# AtxPowerDispatcher3.net
KiCad netlist of a schematic drawn in EAGLE
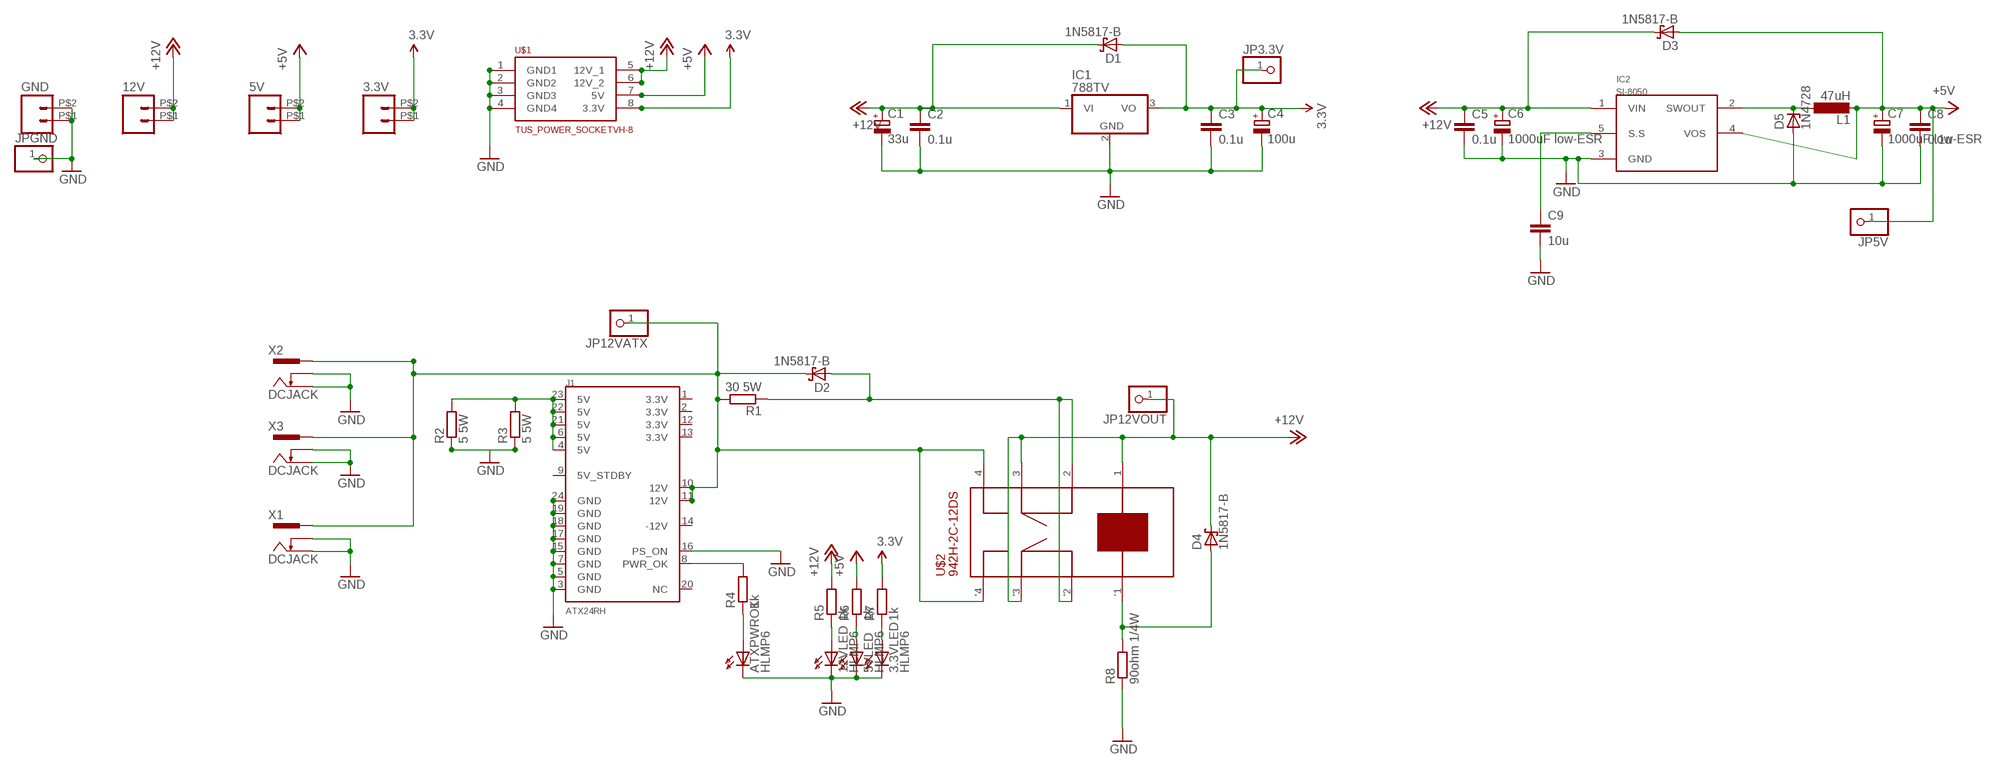
[diagram p0: schematic, sheet 1]

(export (version "E")
  (design (tool "Eeschema 10.0.6"))
  (components
    (comp (ref "3.3V")
      (value "M02PTH2")
      (footprint "eagle-import:1X02_BIG")
      (libsource (lib "eagle-import") (part "M02PTH2"))
    )
    (comp (ref "3.3VLED")
      (value "HLMP6")
      (footprint "eagle-import:HLMP6")
      (fields
        (field (name "MF") "AGILENT TECHNOLOGIES")
        (field (name "MPN") "HLMP-6500")
        (field (name "MF_1") "AGILENT TECHNOLOGIES")
        (field (name "MPN_1") "HLMP-6500")
        (field (name "OC_FARNELL") "1652490")
        (field (name "OC_NEWARK") "40K0088")
      )
      (libsource (lib "eagle-import") (part "HLMP6"))
    )
    (comp (ref "5V")
      (value "M02PTH2")
      (footprint "eagle-import:1X02_BIG")
      (libsource (lib "eagle-import") (part "M02PTH2"))
    )
    (comp (ref "5VLED")
      (value "HLMP6")
      (footprint "eagle-import:HLMP6")
      (fields
        (field (name "MF") "AGILENT TECHNOLOGIES")
        (field (name "MPN") "HLMP-6500")
        (field (name "MF_1") "AGILENT TECHNOLOGIES")
        (field (name "MPN_1") "HLMP-6500")
        (field (name "OC_FARNELL") "1652490")
        (field (name "OC_NEWARK") "40K0088")
      )
      (libsource (lib "eagle-import") (part "HLMP6"))
    )
    (comp (ref "12V")
      (value "M02PTH2")
      (footprint "eagle-import:1X02_BIG")
      (libsource (lib "eagle-import") (part "M02PTH2"))
    )
    (comp (ref "12VLED")
      (value "HLMP6")
      (footprint "eagle-import:HLMP6")
      (fields (field (name "MF") "AGILENT TECHNOLOGIES") (field (name "MPN") "HLMP-6500"))
      (libsource (lib "eagle-import") (part "HLMP6"))
    )
    (comp (ref "ATXPWROK")
      (value "HLMP6")
      (footprint "eagle-import:HLMP6")
      (fields
        (field (name "MF") "AGILENT TECHNOLOGIES")
        (field (name "MPN") "HLMP-6500")
        (field (name "MF_1") "AGILENT TECHNOLOGIES")
        (field (name "MPN_1") "HLMP-6500")
        (field (name "OC_FARNELL") "1652490")
        (field (name "OC_NEWARK") "40K0088")
      )
      (libsource (lib "eagle-import") (part "HLMP6"))
    )
    (comp (ref "C1")
      (value "33u")
      (footprint "eagle-import:E2,5-6E")
      (libsource (lib "eagle-import") (part "CPOL-EUE2,5-6E"))
    )
    (comp (ref "C2")
      (value "0.1u")
      (footprint "eagle-import:C0603")
      (libsource (lib "eagle-import") (part "C-EUC0603"))
    )
    (comp (ref "C3")
      (value "0.1u")
      (footprint "eagle-import:C0603")
      (libsource (lib "eagle-import") (part "C-EUC0603"))
    )
    (comp (ref "C4")
      (value "100u")
      (footprint "eagle-import:E2,5-6E")
      (libsource (lib "eagle-import") (part "CPOL-EUE2,5-6E"))
    )
    (comp (ref "C5")
      (value "0.1u")
      (footprint "eagle-import:C0603")
      (libsource (lib "eagle-import") (part "C-EUC0603"))
    )
    (comp (ref "C6")
      (value "1000uF low-ESR")
      (footprint "eagle-import:E5-10,5")
      (libsource (lib "eagle-import") (part "CPOL-EUE5-10.5"))
    )
    (comp (ref "C7")
      (value "1000uF low-ESR")
      (footprint "eagle-import:E5-10,5")
      (libsource (lib "eagle-import") (part "CPOL-EUE5-10.5"))
    )
    (comp (ref "C8")
      (value "0.1u")
      (footprint "eagle-import:C0603")
      (libsource (lib "eagle-import") (part "C-EUC0603"))
    )
    (comp (ref "C9")
      (value "10u")
      (footprint "eagle-import:C1206")
      (libsource (lib "eagle-import") (part "C-EUC1206"))
    )
    (comp (ref "D1")
      (value "1N5817-B")
      (footprint "eagle-import:DO41-7.6")
      (libsource (lib "eagle-import") (part "1N5817-B"))
    )
    (comp (ref "D2")
      (value "1N5817-B")
      (footprint "eagle-import:DO41-7.6")
      (libsource (lib "eagle-import") (part "1N5817-B"))
    )
    (comp (ref "D3")
      (value "1N5817-B")
      (footprint "eagle-import:DO41-7.6")
      (libsource (lib "eagle-import") (part "1N5817-B"))
    )
    (comp (ref "D4")
      (value "1N5817-B")
      (footprint "eagle-import:DO41-7.6")
      (libsource (lib "eagle-import") (part "1N5817-B"))
    )
    (comp (ref "D5")
      (value "1N4728")
      (footprint "eagle-import:DO41Z10")
      (libsource (lib "eagle-import") (part "1N4728"))
    )
    (comp (ref "GND")
      (value "M02PTH2")
      (footprint "eagle-import:1X02_BIG")
      (libsource (lib "eagle-import") (part "M02PTH2"))
    )
    (comp (ref "IC1")
      (value "788TV")
      (footprint "eagle-import:TO220V")
      (libsource (lib "eagle-import") (part "78TV8"))
    )
    (comp (ref "IC2")
      (value "SI-8050")
      (footprint "eagle-import:TO220-5")
      (libsource (lib "eagle-import") (part "SI-8050"))
    )
    (comp (ref "J1")
      (value "ATX24RH")
      (footprint "eagle-import:ATX24_RIGHT_ANGLE")
      (libsource (lib "eagle-import") (part "ATX24RH"))
    )
    (comp (ref "JP3.3V")
      (value "PINHD-1X1")
      (footprint "eagle-import:1X01")
      (libsource (lib "eagle-import") (part "PINHD-1X1"))
    )
    (comp (ref "JP5V")
      (value "PINHD-1X1")
      (footprint "eagle-import:1X01")
      (libsource (lib "eagle-import") (part "PINHD-1X1"))
    )
    (comp (ref "JP12VATX")
      (value "PINHD-1X1")
      (footprint "eagle-import:1X01")
      (libsource (lib "eagle-import") (part "PINHD-1X1"))
    )
    (comp (ref "JP12VOUT")
      (value "PINHD-1X1")
      (footprint "eagle-import:1X01")
      (libsource (lib "eagle-import") (part "PINHD-1X1"))
    )
    (comp (ref "JPGND")
      (value "PINHD-1X1")
      (footprint "eagle-import:1X01")
      (libsource (lib "eagle-import") (part "PINHD-1X1"))
    )
    (comp (ref "L1")
      (value "47uH")
      (footprint "eagle-import:2200-12.7")
      (libsource (lib "eagle-import") (part "L-EU2200-12.7"))
    )
    (comp (ref "R1")
      (value "30 5W")
      (footprint "eagle-import:0922_22")
      (libsource (lib "eagle-import") (part "resistor_R-EU_0922/22"))
    )
    (comp (ref "R2")
      (value "5 5W")
      (footprint "eagle-import:0922_22")
      (libsource (lib "eagle-import") (part "resistor_R-EU_0922/22"))
    )
    (comp (ref "R3")
      (value "5 5W")
      (footprint "eagle-import:0922_22")
      (libsource (lib "eagle-import") (part "resistor_R-EU_0922/22"))
    )
    (comp (ref "R4")
      (value "1k")
      (footprint "eagle-import:R0603")
      (libsource (lib "eagle-import") (part "R-EU_R0603"))
    )
    (comp (ref "R5")
      (value "1k")
      (footprint "eagle-import:R0603")
      (libsource (lib "eagle-import") (part "R-EU_R0603"))
    )
    (comp (ref "R6")
      (value "1k")
      (footprint "eagle-import:R0603")
      (libsource (lib "eagle-import") (part "R-EU_R0603"))
    )
    (comp (ref "R7")
      (value "1k")
      (footprint "eagle-import:R0603")
      (libsource (lib "eagle-import") (part "R-EU_R0603"))
    )
    (comp (ref "R8")
      (value "90ohm 1/4W")
      (footprint "eagle-import:0207_10")
      (libsource (lib "eagle-import") (part "resistor_R-EU_0207/10"))
    )
    (comp (ref "U$1")
      (value "TUS_POWER_SOCKETVH-8")
      (footprint "eagle-import:VH_8")
      (libsource (lib "eagle-import") (part "TUS_POWER_SOCKETVH-8"))
    )
    (comp (ref "U$2")
      (value "942H-2C-12DS")
      (footprint "eagle-import:942H")
      (libsource (lib "eagle-import") (part "942H-2C-12DS"))
    )
    (comp (ref "X1")
      (value "DCJACK")
      (footprint "eagle-import:2DC-0005D100")
      (libsource (lib "eagle-import") (part "DCJACK"))
    )
    (comp (ref "X2")
      (value "DCJACK")
      (footprint "eagle-import:2DC-0005D100")
      (libsource (lib "eagle-import") (part "DCJACK"))
    )
    (comp (ref "X3")
      (value "DCJACK")
      (footprint "eagle-import:2DC-0005D100")
      (libsource (lib "eagle-import") (part "DCJACK"))
    )
  )
  (nets
    (net (code "1") (name "+5V") (class "Default")
      (node (ref "5V") (pin "P$1") (pinfunction "1_P$1") (pintype "passive"))
      (node (ref "5V") (pin "P$2") (pinfunction "2_P$2") (pintype "passive"))
      (node (ref "C7") (pin "+") (pinfunction "+_+") (pintype "passive"))
      (node (ref "C8") (pin "1") (pinfunction "1_1") (pintype "passive"))
      (node (ref "D3") (pin "A") (pinfunction "A_A") (pintype "passive"))
      (node (ref "IC2") (pin "4") (pinfunction "VOS_4") (pintype "bidirectional"))
      (node (ref "JP5V") (pin "1") (pinfunction "1_1") (pintype "passive"))
      (node (ref "L1") (pin "2") (pinfunction "2_2") (pintype "passive"))
      (node (ref "R6") (pin "2") (pinfunction "2_2") (pintype "passive"))
      (node (ref "U$1") (pin "7") (pinfunction "5V_7") (pintype "power_in"))
    )
    (net (code "2") (name "+12V") (class "Default")
      (node (ref "12V") (pin "P$1") (pinfunction "1_P$1") (pintype "passive"))
      (node (ref "12V") (pin "P$2") (pinfunction "2_P$2") (pintype "passive"))
      (node (ref "C1") (pin "+") (pinfunction "+_+") (pintype "passive"))
      (node (ref "C2") (pin "1") (pinfunction "1_1") (pintype "passive"))
      (node (ref "C5") (pin "1") (pinfunction "1_1") (pintype "passive"))
      (node (ref "C6") (pin "+") (pinfunction "+_+") (pintype "passive"))
      (node (ref "D1") (pin "C") (pinfunction "C_C") (pintype "passive"))
      (node (ref "D3") (pin "C") (pinfunction "C_C") (pintype "passive"))
      (node (ref "D4") (pin "C") (pinfunction "C_C") (pintype "passive"))
      (node (ref "IC1") (pin "1") (pinfunction "VI_1") (pintype "input"))
      (node (ref "IC2") (pin "1") (pinfunction "VIN_1") (pintype "bidirectional"))
      (node (ref "JP12VOUT") (pin "1") (pinfunction "1_1") (pintype "passive"))
      (node (ref "R5") (pin "2") (pinfunction "2_2") (pintype "passive"))
      (node (ref "U$1") (pin "5") (pinfunction "12V_1_5") (pintype "power_in"))
      (node (ref "U$1") (pin "6") (pinfunction "12V_2_6") (pintype "power_in"))
      (node (ref "U$2") (pin "'3") (pinfunction "'2_'3") (pintype "bidirectional"))
      (node (ref "U$2") (pin "1") (pinfunction "4_1") (pintype "bidirectional"))
      (node (ref "U$2") (pin "3") (pinfunction "2_3") (pintype "bidirectional"))
    )
    (net (code "3") (name "3.3V") (class "Default")
      (node (ref "3.3V") (pin "P$1") (pinfunction "1_P$1") (pintype "passive"))
      (node (ref "3.3V") (pin "P$2") (pinfunction "2_P$2") (pintype "passive"))
      (node (ref "C3") (pin "1") (pinfunction "1_1") (pintype "passive"))
      (node (ref "C4") (pin "+") (pinfunction "+_+") (pintype "passive"))
      (node (ref "D1") (pin "A") (pinfunction "A_A") (pintype "passive"))
      (node (ref "IC1") (pin "3") (pinfunction "VO_3") (pintype "passive"))
      (node (ref "JP3.3V") (pin "1") (pinfunction "1_1") (pintype "passive"))
      (node (ref "R7") (pin "2") (pinfunction "2_2") (pintype "passive"))
      (node (ref "U$1") (pin "8") (pinfunction "3.3V_8") (pintype "power_in"))
    )
    (net (code "4") (name "GND") (class "Default")
      (node (ref "12VLED") (pin "K") (pinfunction "K_K") (pintype "passive"))
      (node (ref "3.3VLED") (pin "K") (pinfunction "K_K") (pintype "passive"))
      (node (ref "5VLED") (pin "K") (pinfunction "K_K") (pintype "passive"))
      (node (ref "ATXPWROK") (pin "K") (pinfunction "K_K") (pintype "passive"))
      (node (ref "C1") (pin "-") (pinfunction "-_-") (pintype "passive"))
      (node (ref "C2") (pin "2") (pinfunction "2_2") (pintype "passive"))
      (node (ref "C3") (pin "2") (pinfunction "2_2") (pintype "passive"))
      (node (ref "C4") (pin "-") (pinfunction "-_-") (pintype "passive"))
      (node (ref "C5") (pin "2") (pinfunction "2_2") (pintype "passive"))
      (node (ref "C6") (pin "-") (pinfunction "-_-") (pintype "passive"))
      (node (ref "C7") (pin "-") (pinfunction "-_-") (pintype "passive"))
      (node (ref "C8") (pin "2") (pinfunction "2_2") (pintype "passive"))
      (node (ref "C9") (pin "2") (pinfunction "2_2") (pintype "passive"))
      (node (ref "D5") (pin "A") (pinfunction "A_A") (pintype "passive"))
      (node (ref "GND") (pin "P$1") (pinfunction "1_P$1") (pintype "passive"))
      (node (ref "GND") (pin "P$2") (pinfunction "2_P$2") (pintype "passive"))
      (node (ref "IC1") (pin "2") (pinfunction "GND_2") (pintype "passive"))
      (node (ref "IC2") (pin "3") (pinfunction "GND_3") (pintype "bidirectional"))
      (node (ref "J1") (pin "15") (pinfunction "GND_15") (pintype "bidirectional"))
      (node (ref "J1") (pin "16") (pinfunction "PS_ON_16") (pintype "bidirectional"))
      (node (ref "J1") (pin "17") (pinfunction "GND_17") (pintype "bidirectional"))
      (node (ref "J1") (pin "18") (pinfunction "GND_18") (pintype "bidirectional"))
      (node (ref "J1") (pin "19") (pinfunction "GND_19") (pintype "bidirectional"))
      (node (ref "J1") (pin "24") (pinfunction "GND_24") (pintype "bidirectional"))
      (node (ref "J1") (pin "3") (pinfunction "GND_3") (pintype "bidirectional"))
      (node (ref "J1") (pin "5") (pinfunction "GND_5") (pintype "bidirectional"))
      (node (ref "J1") (pin "7") (pinfunction "GND_7") (pintype "bidirectional"))
      (node (ref "JPGND") (pin "1") (pinfunction "1_1") (pintype "passive"))
      (node (ref "R2") (pin "1") (pinfunction "1_1") (pintype "passive"))
      (node (ref "R3") (pin "1") (pinfunction "1_1") (pintype "passive"))
      (node (ref "R8") (pin "1") (pinfunction "1_1") (pintype "passive"))
      (node (ref "U$1") (pin "1") (pinfunction "GND1_1") (pintype "power_in"))
      (node (ref "U$1") (pin "2") (pinfunction "GND2_2") (pintype "power_in"))
      (node (ref "U$1") (pin "3") (pinfunction "GND3_3") (pintype "power_in"))
      (node (ref "U$1") (pin "4") (pinfunction "GND4_4") (pintype "power_in"))
      (node (ref "X1") (pin "2") (pinfunction "2_2") (pintype "passive"))
      (node (ref "X1") (pin "3") (pinfunction "3_3") (pintype "passive"))
      (node (ref "X2") (pin "2") (pinfunction "2_2") (pintype "passive"))
      (node (ref "X2") (pin "3") (pinfunction "3_3") (pintype "passive"))
      (node (ref "X3") (pin "2") (pinfunction "2_2") (pintype "passive"))
      (node (ref "X3") (pin "3") (pinfunction "3_3") (pintype "passive"))
    )
    (net (code "5") (name "Net-(3.3VLED-PadA)") (class "Default")
      (node (ref "3.3VLED") (pin "A") (pinfunction "A_A") (pintype "passive"))
      (node (ref "R7") (pin "1") (pinfunction "1_1") (pintype "passive"))
    )
    (net (code "6") (name "Net-(5VLED-PadA)") (class "Default")
      (node (ref "5VLED") (pin "A") (pinfunction "A_A") (pintype "passive"))
      (node (ref "R6") (pin "1") (pinfunction "1_1") (pintype "passive"))
    )
    (net (code "7") (name "Net-(12VLED-PadA)") (class "Default")
      (node (ref "12VLED") (pin "A") (pinfunction "A_A") (pintype "passive"))
      (node (ref "R5") (pin "1") (pinfunction "1_1") (pintype "passive"))
    )
    (net (code "8") (name "Net-(ATXPWROK-PadA)") (class "Default")
      (node (ref "ATXPWROK") (pin "A") (pinfunction "A_A") (pintype "passive"))
      (node (ref "R4") (pin "1") (pinfunction "1_1") (pintype "passive"))
    )
    (net (code "9") (name "Net-(IC2-S.S)") (class "Default")
      (node (ref "C9") (pin "1") (pinfunction "1_1") (pintype "passive"))
      (node (ref "IC2") (pin "5") (pinfunction "S.S_5") (pintype "bidirectional"))
    )
    (net (code "10") (name "Net-(IC2-SWOUT)") (class "Default")
      (node (ref "D5") (pin "C") (pinfunction "C_C") (pintype "passive"))
      (node (ref "IC2") (pin "2") (pinfunction "SWOUT_2") (pintype "bidirectional"))
      (node (ref "L1") (pin "1") (pinfunction "1_1") (pintype "passive"))
    )
    (net (code "11") (name "Net-(J1-5V-Pad21)") (class "Default")
      (node (ref "J1") (pin "21") (pinfunction "5V_21") (pintype "bidirectional"))
      (node (ref "J1") (pin "22") (pinfunction "5V_22") (pintype "bidirectional"))
      (node (ref "J1") (pin "23") (pinfunction "5V_23") (pintype "bidirectional"))
      (node (ref "J1") (pin "4") (pinfunction "5V_4") (pintype "bidirectional"))
      (node (ref "J1") (pin "6") (pinfunction "5V_6") (pintype "bidirectional"))
      (node (ref "R2") (pin "2") (pinfunction "2_2") (pintype "passive"))
      (node (ref "R3") (pin "2") (pinfunction "2_2") (pintype "passive"))
    )
    (net (code "12") (name "Net-(J1-PWR_OK)") (class "Default")
      (node (ref "J1") (pin "8") (pinfunction "PWR_OK_8") (pintype "bidirectional"))
      (node (ref "R4") (pin "2") (pinfunction "2_2") (pintype "passive"))
    )
    (net (code "13") (name "Net-(U$2-'1)") (class "Default")
      (node (ref "D2") (pin "C") (pinfunction "C_C") (pintype "passive"))
      (node (ref "J1") (pin "10") (pinfunction "12V_10") (pintype "bidirectional"))
      (node (ref "J1") (pin "11") (pinfunction "12V_11") (pintype "bidirectional"))
      (node (ref "JP12VATX") (pin "1") (pinfunction "1_1") (pintype "passive"))
      (node (ref "R1") (pin "2") (pinfunction "2_2") (pintype "passive"))
      (node (ref "U$2") (pin "'4") (pinfunction "'1_'4") (pintype "bidirectional"))
      (node (ref "U$2") (pin "4") (pinfunction "1_4") (pintype "bidirectional"))
      (node (ref "X1") (pin "1") (pinfunction "1_1") (pintype "passive"))
      (node (ref "X2") (pin "1") (pinfunction "1_1") (pintype "passive"))
      (node (ref "X3") (pin "1") (pinfunction "1_1") (pintype "passive"))
    )
    (net (code "14") (name "Net-(U$2-'3)") (class "Default")
      (node (ref "D2") (pin "A") (pinfunction "A_A") (pintype "passive"))
      (node (ref "R1") (pin "1") (pinfunction "1_1") (pintype "passive"))
      (node (ref "U$2") (pin "'2") (pinfunction "'3_'2") (pintype "bidirectional"))
      (node (ref "U$2") (pin "2") (pinfunction "3_2") (pintype "bidirectional"))
    )
    (net (code "15") (name "Net-(U$2-'4)") (class "Default")
      (node (ref "D4") (pin "A") (pinfunction "A_A") (pintype "passive"))
      (node (ref "R8") (pin "2") (pinfunction "2_2") (pintype "passive"))
      (node (ref "U$2") (pin "'1") (pinfunction "'4_'1") (pintype "bidirectional"))
    )
    (net (code "16") (name "unconnected-(J1--12V-Pad14)") (class "Default")
      (node (ref "J1") (pin "14") (pinfunction "-12V_14") (pintype "bidirectional"))
    )
    (net (code "17") (name "unconnected-(J1-3.3V-Pad1)") (class "Default")
      (node (ref "J1") (pin "1") (pinfunction "3.3V_1") (pintype "bidirectional"))
    )
    (net (code "18") (name "unconnected-(J1-3.3V-Pad2)") (class "Default")
      (node (ref "J1") (pin "2") (pinfunction "3.3V_2") (pintype "bidirectional"))
    )
    (net (code "19") (name "unconnected-(J1-3.3V-Pad12)") (class "Default")
      (node (ref "J1") (pin "12") (pinfunction "3.3V_12") (pintype "bidirectional"))
    )
    (net (code "20") (name "unconnected-(J1-3.3V-Pad13)") (class "Default")
      (node (ref "J1") (pin "13") (pinfunction "3.3V_13") (pintype "bidirectional"))
    )
    (net (code "21") (name "unconnected-(J1-5V_STDBY-Pad9)") (class "Default")
      (node (ref "J1") (pin "9") (pinfunction "5V_STDBY_9") (pintype "bidirectional"))
    )
    (net (code "22") (name "unconnected-(J1-NC-Pad20)") (class "Default")
      (node (ref "J1") (pin "20") (pinfunction "NC_20") (pintype "bidirectional"))
    )
  )
)
